# outputdiode.net
KiCad netlist of a schematic drawn in Altium Designer
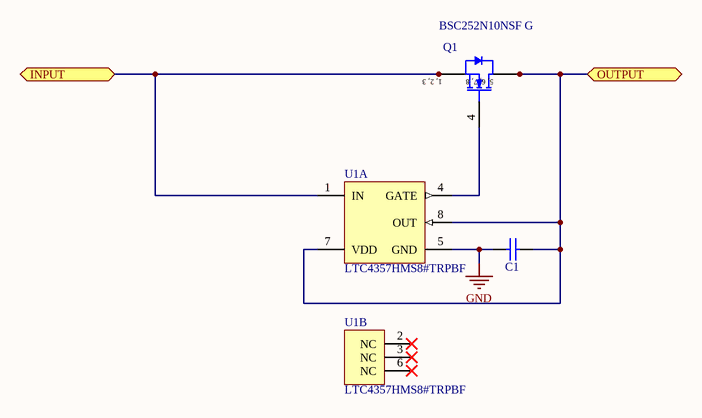
[diagram p0: outputdiode.SchDoc]

(export (version "E")
  (design (tool "Eeschema 10.0.6"))
  (components
    (comp (ref "C1")
      (value "CAP 470nF 100V 0805(2012)")
      (footprint "CAPC0805(2012)145_M")
      (description "CAP 470nF 100V ±10% 0805 (2012 Metric) Thickness 1.45mm SMD")
      (fields (field (name "TOLERANCE") "Â±10%"))
      (libsource (lib "Altium Content Vault") (part "CAP"))
    )
    (comp (ref "Q1")
      (value "BSC252N10NSF G")
      (footprint "INF-PG-TDSON-8-1_V")
      (fields (field (name "MANUFACTURER") "Infineon"))
      (libsource (lib "Altium Content Vault") (part "INF-NEMOS-SSSGDDDD-8"))
    )
    (comp (ref "U1")
      (value "LTC4357HMS8#TRPBF")
      (footprint "LT-MS8-8_M")
      (fields (field (name "MANUFACTURER") "Linear Technology"))
      (libsource (lib "Altium Content Vault") (part "LT-LTC4357-MS8-8"))
    )
  )
  (nets
    (net (code "1") (name "/INPUT") (class "Default")
      (node (ref "Q1") (pin "1") (pinfunction "SOURCE_1") (pintype "passive"))
      (node (ref "Q1") (pin "2") (pinfunction "SOURCE_2") (pintype "passive"))
      (node (ref "Q1") (pin "3") (pinfunction "SOURCE_3") (pintype "passive"))
      (node (ref "U1") (pin "1") (pinfunction "IN_1") (pintype "power_in"))
    )
    (net (code "2") (name "/OUTPUT") (class "Default")
      (node (ref "C1") (pin "2") (pinfunction "2_2") (pintype "passive"))
      (node (ref "Q1") (pin "5") (pinfunction "DRAIN_5") (pintype "passive"))
      (node (ref "Q1") (pin "6") (pinfunction "DRAIN_6") (pintype "passive"))
      (node (ref "Q1") (pin "7") (pinfunction "DRAIN_7") (pintype "passive"))
      (node (ref "Q1") (pin "8") (pinfunction "DRAIN_8") (pintype "passive"))
      (node (ref "U1") (pin "7") (pinfunction "VDD_7") (pintype "power_in"))
      (node (ref "U1") (pin "8") (pinfunction "OUT_8") (pintype "input"))
    )
    (net (code "3") (name "GND") (class "Default")
      (node (ref "C1") (pin "1") (pinfunction "1_1") (pintype "passive"))
      (node (ref "U1") (pin "5") (pinfunction "GND_5") (pintype "power_in"))
    )
    (net (code "4") (name "Net-(Q1-GATE)") (class "Default")
      (node (ref "Q1") (pin "4") (pinfunction "GATE_4") (pintype "passive"))
      (node (ref "U1") (pin "4") (pinfunction "GATE_4") (pintype "output"))
    )
    (net (code "5") (name "unconnected-(U1B-NC-Pad2)") (class "Default")
      (node (ref "U1") (pin "2") (pinfunction "NC_2") (pintype "passive+no_connect"))
    )
    (net (code "6") (name "unconnected-(U1B-NC-Pad3)") (class "Default")
      (node (ref "U1") (pin "3") (pinfunction "NC_3") (pintype "passive+no_connect"))
    )
    (net (code "7") (name "unconnected-(U1B-NC-Pad6)") (class "Default")
      (node (ref "U1") (pin "6") (pinfunction "NC_6") (pintype "passive+no_connect"))
    )
  )
)
